# LCD1602.net
KiCad netlist of a schematic drawn in Altium Designer
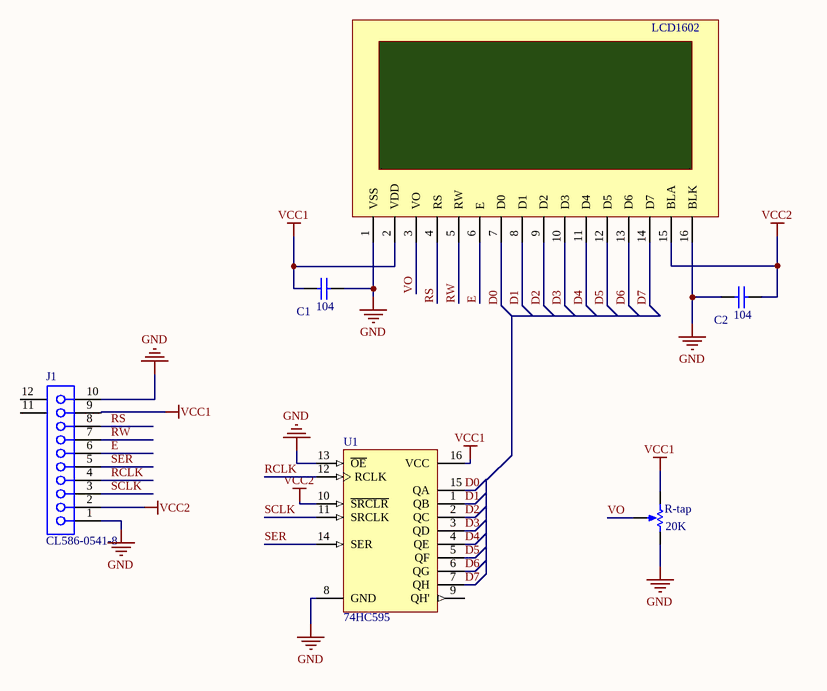
[diagram p0: LCD1602.SchDoc]

(export (version "E")
  (design (tool "Eeschema 10.0.6"))
  (components
    (comp (ref "C1")
      (value "104")
      (footprint "C0805")
      (description "Capacitor")
      (fields (field (name "Comment") "Cap") (field (name "PUBLISHER") "Altium Limited"))
      (libsource (lib "Miscellaneous Devices") (part "Cap"))
    )
    (comp (ref "C2")
      (value "104")
      (footprint "C0805")
      (description "Capacitor")
      (fields (field (name "Comment") "Cap") (field (name "PUBLISHER") "Altium Limited"))
      (libsource (lib "Miscellaneous Devices") (part "Cap"))
    )
    (comp (ref "J1")
      (value "CL586-0541-8")
      (footprint "FH12-22(10)SA-1SH")
      (description "FH12 Series, \"Flip-Lock\" SMT/ZIF FFC/FPC Connector - 1.0mm Spaced Bottom Eccentric Contact")
      (fields (field (name "PUBLISHER") "Altium Limited"))
      (libsource (lib "HRS FPC-FFC FH12 Series") (part "CL586-0541-8"))
    )
    (comp (ref "LCD1")
      (value "LCD1602")
      (footprint "LCD 1602 - cut")
      (libsource (lib "self") (part "LCD1602"))
    )
    (comp (ref "R-tap")
      (value "20K")
      (footprint "res-tap")
      (description "Potentiometer")
      (fields (field (name "Comment") "RPot") (field (name "PUBLISHER") "Altium Limited"))
      (libsource (lib "Miscellaneous Devices") (part "RPot"))
    )
    (comp (ref "U1")
      (value "74HC595")
      (footprint "SO16_N")
      (description "8 Bit Shift Register with Output Latches (3 STATE)")
      (fields (field (name "PUBLISHER") "Altium Limited"))
      (libsource (lib "ST Logic Register") (part "M74HC595B1R"))
    )
  )
  (nets
    (net (code "1") (name "/D0") (class "Default")
      (node (ref "LCD1") (pin "7") (pinfunction "D0_7") (pintype "passive"))
      (node (ref "U1") (pin "15") (pinfunction "QA_15") (pintype "tri_state"))
    )
    (net (code "2") (name "/D1") (class "Default")
      (node (ref "LCD1") (pin "8") (pinfunction "D1_8") (pintype "passive"))
      (node (ref "U1") (pin "1") (pinfunction "QB_1") (pintype "tri_state"))
    )
    (net (code "3") (name "/D2") (class "Default")
      (node (ref "LCD1") (pin "9") (pinfunction "D2_9") (pintype "passive"))
      (node (ref "U1") (pin "2") (pinfunction "QC_2") (pintype "tri_state"))
    )
    (net (code "4") (name "/D3") (class "Default")
      (node (ref "LCD1") (pin "10") (pinfunction "D3_10") (pintype "passive"))
      (node (ref "U1") (pin "3") (pinfunction "QD_3") (pintype "tri_state"))
    )
    (net (code "5") (name "/D4") (class "Default")
      (node (ref "LCD1") (pin "11") (pinfunction "D4_11") (pintype "passive"))
      (node (ref "U1") (pin "4") (pinfunction "QE_4") (pintype "tri_state"))
    )
    (net (code "6") (name "/D5") (class "Default")
      (node (ref "LCD1") (pin "12") (pinfunction "D5_12") (pintype "passive"))
      (node (ref "U1") (pin "5") (pinfunction "QF_5") (pintype "tri_state"))
    )
    (net (code "7") (name "/D6") (class "Default")
      (node (ref "LCD1") (pin "13") (pinfunction "D6_13") (pintype "passive"))
      (node (ref "U1") (pin "6") (pinfunction "QG_6") (pintype "tri_state"))
    )
    (net (code "8") (name "/D7") (class "Default")
      (node (ref "LCD1") (pin "14") (pinfunction "D7_14") (pintype "passive"))
      (node (ref "U1") (pin "7") (pinfunction "QH_7") (pintype "tri_state"))
    )
    (net (code "9") (name "/E") (class "Default")
      (node (ref "J1") (pin "6") (pinfunction "6_6") (pintype "passive"))
      (node (ref "LCD1") (pin "6") (pinfunction "E_6") (pintype "passive"))
    )
    (net (code "10") (name "/RCLK") (class "Default")
      (node (ref "J1") (pin "4") (pinfunction "4_4") (pintype "passive"))
      (node (ref "U1") (pin "12") (pinfunction "RCLK_12") (pintype "input"))
    )
    (net (code "11") (name "/RS") (class "Default")
      (node (ref "J1") (pin "8") (pinfunction "8_8") (pintype "passive"))
      (node (ref "LCD1") (pin "4") (pinfunction "RS_4") (pintype "passive"))
    )
    (net (code "12") (name "/RW") (class "Default")
      (node (ref "J1") (pin "7") (pinfunction "7_7") (pintype "passive"))
      (node (ref "LCD1") (pin "5") (pinfunction "RW_5") (pintype "passive"))
    )
    (net (code "13") (name "/SCLK") (class "Default")
      (node (ref "J1") (pin "3") (pinfunction "3_3") (pintype "passive"))
      (node (ref "U1") (pin "11") (pinfunction "SRCLK_11") (pintype "input"))
    )
    (net (code "14") (name "/SER") (class "Default")
      (node (ref "J1") (pin "5") (pinfunction "5_5") (pintype "passive"))
      (node (ref "U1") (pin "14") (pinfunction "SER_14") (pintype "input"))
    )
    (net (code "15") (name "/VO") (class "Default")
      (node (ref "LCD1") (pin "3") (pinfunction "VO_3") (pintype "passive"))
      (node (ref "R-tap") (pin "2") (pinfunction "BOT_2") (pintype "passive"))
    )
    (net (code "16") (name "GND") (class "Default")
      (node (ref "C1") (pin "2") (pinfunction "2_2") (pintype "passive"))
      (node (ref "C2") (pin "1") (pinfunction "1_1") (pintype "passive"))
      (node (ref "J1") (pin "1") (pinfunction "1_1") (pintype "passive"))
      (node (ref "J1") (pin "10") (pinfunction "10_10") (pintype "passive"))
      (node (ref "LCD1") (pin "1") (pinfunction "VSS_1") (pintype "passive"))
      (node (ref "LCD1") (pin "16") (pinfunction "BLK_16") (pintype "passive"))
      (node (ref "R-tap") (pin "3") (pinfunction "TAP_3") (pintype "passive"))
      (node (ref "U1") (pin "13") (pinfunction "~{OE}_13") (pintype "input"))
      (node (ref "U1") (pin "8") (pinfunction "GND_8") (pintype "power_in"))
    )
    (net (code "17") (name "VCC1") (class "Default")
      (node (ref "C1") (pin "1") (pinfunction "1_1") (pintype "passive"))
      (node (ref "J1") (pin "9") (pinfunction "9_9") (pintype "passive"))
      (node (ref "LCD1") (pin "2") (pinfunction "VDD_2") (pintype "passive"))
      (node (ref "R-tap") (pin "1") (pinfunction "TOP_1") (pintype "passive"))
      (node (ref "U1") (pin "16") (pinfunction "VCC_16") (pintype "power_in"))
    )
    (net (code "18") (name "VCC2") (class "Default")
      (node (ref "C2") (pin "2") (pinfunction "2_2") (pintype "passive"))
      (node (ref "J1") (pin "2") (pinfunction "2_2") (pintype "passive"))
      (node (ref "LCD1") (pin "15") (pinfunction "BLA_15") (pintype "passive"))
      (node (ref "U1") (pin "10") (pinfunction "~{SRCLR}_10") (pintype "input"))
    )
    (net (code "19") (name "unconnected-(J1-MH1-Pad11)") (class "Default")
      (node (ref "J1") (pin "11") (pinfunction "MH1_11") (pintype "passive"))
    )
    (net (code "20") (name "unconnected-(J1-MH2-Pad12)") (class "Default")
      (node (ref "J1") (pin "12") (pinfunction "MH2_12") (pintype "passive"))
    )
    (net (code "21") (name "unconnected-(U1-QH'-Pad9)") (class "Default")
      (node (ref "U1") (pin "9") (pinfunction "QH'_9") (pintype "output"))
    )
  )
)
